# MCU_Power.net
KiCad netlist of a schematic drawn in Altium Designer
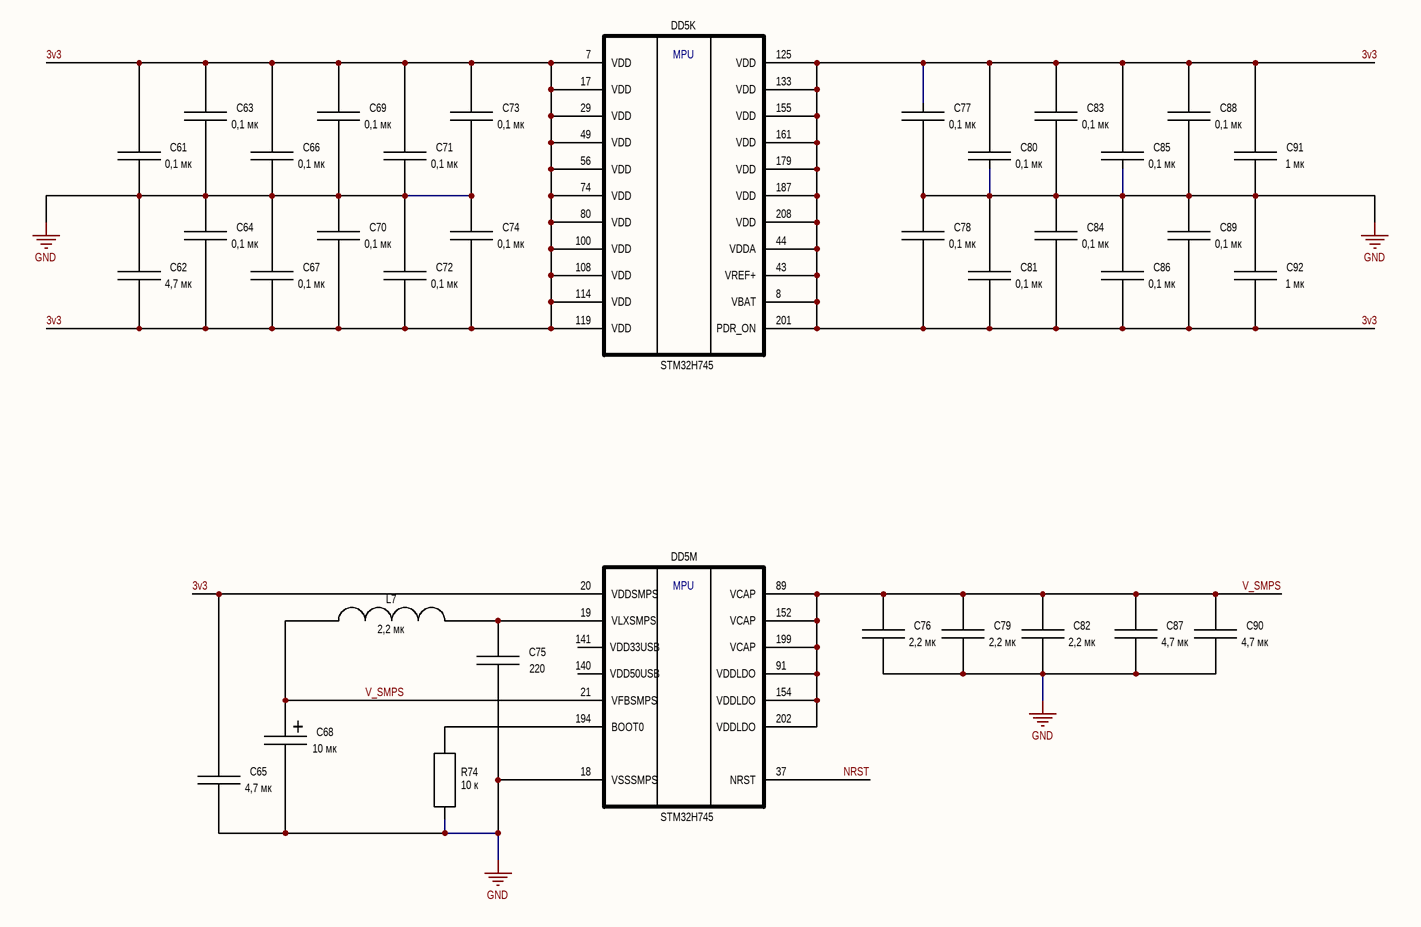
[diagram p0: MCU_Power.SchDoc]

(export (version "E")
  (design (tool "Eeschema 10.0.6"))
  (components
    (comp (ref "C61")
      (value "0,1 мк")
      (footprint "C0603")
      (fields
        (field (name "TOLERANCE") "±10%")
        (field (name "VOLTAGE") "50 В")
        (field (name "PARTNUMBER") "GRM188R71H104KA93D")
      )
      (libsource (lib "5ko") (part "C"))
    )
    (comp (ref "C62")
      (value "4,7 мк")
      (footprint "C0603")
      (fields
        (field (name "TOLERANCE") "±10%")
        (field (name "VOLTAGE") "16 В")
        (field (name "PARTNUMBER") "GRM188Z71C475KE21D")
      )
      (libsource (lib "5ko") (part "C"))
    )
    (comp (ref "C63")
      (value "0,1 мк")
      (footprint "C0603")
      (fields
        (field (name "TOLERANCE") "±10%")
        (field (name "VOLTAGE") "50 В")
        (field (name "PARTNUMBER") "GRM188R71H104KA93D")
      )
      (libsource (lib "5ko") (part "C"))
    )
    (comp (ref "C64")
      (value "0,1 мк")
      (footprint "C0603")
      (fields
        (field (name "TOLERANCE") "±10%")
        (field (name "VOLTAGE") "50 В")
        (field (name "PARTNUMBER") "GRM188R71H104KA93D")
      )
      (libsource (lib "5ko") (part "C"))
    )
    (comp (ref "C65")
      (value "4,7 мк")
      (footprint "C0603")
      (fields
        (field (name "TOLERANCE") "±10%")
        (field (name "VOLTAGE") "16 В")
        (field (name "PARTNUMBER") "GRM188Z71C475KE21D")
      )
      (libsource (lib "5ko") (part "C"))
    )
    (comp (ref "C66")
      (value "0,1 мк")
      (footprint "C0603")
      (fields
        (field (name "TOLERANCE") "±10%")
        (field (name "VOLTAGE") "50 В")
        (field (name "PARTNUMBER") "GRM188R71H104KA93D")
      )
      (libsource (lib "5ko") (part "C"))
    )
    (comp (ref "C67")
      (value "0,1 мк")
      (footprint "C0603")
      (fields
        (field (name "TOLERANCE") "±10%")
        (field (name "VOLTAGE") "50 В")
        (field (name "PARTNUMBER") "GRM188R71H104KA93D")
      )
      (libsource (lib "5ko") (part "C"))
    )
    (comp (ref "C68")
      (value "10 мк")
      (footprint "Case A")
      (fields
        (field (name "TOLERANCE") "±10%")
        (field (name "VOLTAGE") "16 V")
        (field (name "PARTNUMBER") "TAJA106K016RNJ")
      )
      (libsource (lib "5ko") (part "C_el"))
    )
    (comp (ref "C69")
      (value "0,1 мк")
      (footprint "C0603")
      (fields
        (field (name "TOLERANCE") "±10%")
        (field (name "VOLTAGE") "50 В")
        (field (name "PARTNUMBER") "GRM188R71H104KA93D")
      )
      (libsource (lib "5ko") (part "C"))
    )
    (comp (ref "C70")
      (value "0,1 мк")
      (footprint "C0603")
      (fields
        (field (name "TOLERANCE") "±10%")
        (field (name "VOLTAGE") "50 В")
        (field (name "PARTNUMBER") "GRM188R71H104KA93D")
      )
      (libsource (lib "5ko") (part "C"))
    )
    (comp (ref "C71")
      (value "0,1 мк")
      (footprint "C0603")
      (fields
        (field (name "TOLERANCE") "±10%")
        (field (name "VOLTAGE") "50 В")
        (field (name "PARTNUMBER") "GRM188R71H104KA93D")
      )
      (libsource (lib "5ko") (part "C"))
    )
    (comp (ref "C72")
      (value "0,1 мк")
      (footprint "C0603")
      (fields
        (field (name "TOLERANCE") "±10%")
        (field (name "VOLTAGE") "50 В")
        (field (name "PARTNUMBER") "GRM188R71H104KA93D")
      )
      (libsource (lib "5ko") (part "C"))
    )
    (comp (ref "C73")
      (value "0,1 мк")
      (footprint "C0603")
      (fields
        (field (name "TOLERANCE") "±10%")
        (field (name "VOLTAGE") "50 В")
        (field (name "PARTNUMBER") "GRM188R71H104KA93D")
      )
      (libsource (lib "5ko") (part "C"))
    )
    (comp (ref "C74")
      (value "0,1 мк")
      (footprint "C0603")
      (fields
        (field (name "TOLERANCE") "±10%")
        (field (name "VOLTAGE") "50 В")
        (field (name "PARTNUMBER") "GRM188R71H104KA93D")
      )
      (libsource (lib "5ko") (part "C"))
    )
    (comp (ref "C75")
      (value "220")
      (footprint "C0603")
      (fields
        (field (name "TOLERANCE") "±5%")
        (field (name "VOLTAGE") "100 В")
        (field (name "PARTNUMBER") "GCM1885C2A221JA16D")
      )
      (libsource (lib "5ko") (part "C"))
    )
    (comp (ref "C76")
      (value "2,2 мк")
      (footprint "C0603")
      (fields
        (field (name "TOLERANCE") "±10%")
        (field (name "VOLTAGE") "10 В")
        (field (name "PARTNUMBER") "GRM188R71A225KE15J")
      )
      (libsource (lib "5ko") (part "C"))
    )
    (comp (ref "C77")
      (value "0,1 мк")
      (footprint "C0603")
      (fields
        (field (name "TOLERANCE") "±10%")
        (field (name "VOLTAGE") "50 В")
        (field (name "PARTNUMBER") "GRM188R71H104KA93D")
      )
      (libsource (lib "5ko") (part "C"))
    )
    (comp (ref "C78")
      (value "0,1 мк")
      (footprint "C0603")
      (fields
        (field (name "TOLERANCE") "±10%")
        (field (name "VOLTAGE") "50 В")
        (field (name "PARTNUMBER") "GRM188R71H104KA93D")
      )
      (libsource (lib "5ko") (part "C"))
    )
    (comp (ref "C79")
      (value "2,2 мк")
      (footprint "C0603")
      (fields
        (field (name "TOLERANCE") "±10%")
        (field (name "VOLTAGE") "10 В")
        (field (name "PARTNUMBER") "GRM188R71A225KE15J")
      )
      (libsource (lib "5ko") (part "C"))
    )
    (comp (ref "C80")
      (value "0,1 мк")
      (footprint "C0603")
      (fields
        (field (name "TOLERANCE") "±10%")
        (field (name "VOLTAGE") "50 В")
        (field (name "PARTNUMBER") "GRM188R71H104KA93D")
      )
      (libsource (lib "5ko") (part "C"))
    )
    (comp (ref "C81")
      (value "0,1 мк")
      (footprint "C0603")
      (fields
        (field (name "TOLERANCE") "±10%")
        (field (name "VOLTAGE") "50 В")
        (field (name "PARTNUMBER") "GRM188R71H104KA93D")
      )
      (libsource (lib "5ko") (part "C"))
    )
    (comp (ref "C82")
      (value "2,2 мк")
      (footprint "C0603")
      (fields
        (field (name "TOLERANCE") "±10%")
        (field (name "VOLTAGE") "10 В")
        (field (name "PARTNUMBER") "GRM188R71A225KE15J")
      )
      (libsource (lib "5ko") (part "C"))
    )
    (comp (ref "C83")
      (value "0,1 мк")
      (footprint "C0603")
      (fields
        (field (name "TOLERANCE") "±10%")
        (field (name "VOLTAGE") "50 В")
        (field (name "PARTNUMBER") "GRM188R71H104KA93D")
      )
      (libsource (lib "5ko") (part "C"))
    )
    (comp (ref "C84")
      (value "0,1 мк")
      (footprint "C0603")
      (fields
        (field (name "TOLERANCE") "±10%")
        (field (name "VOLTAGE") "50 В")
        (field (name "PARTNUMBER") "GRM188R71H104KA93D")
      )
      (libsource (lib "5ko") (part "C"))
    )
    (comp (ref "C85")
      (value "0,1 мк")
      (footprint "C0603")
      (fields
        (field (name "TOLERANCE") "±10%")
        (field (name "VOLTAGE") "50 В")
        (field (name "PARTNUMBER") "GRM188R71H104KA93D")
      )
      (libsource (lib "5ko") (part "C"))
    )
    (comp (ref "C86")
      (value "0,1 мк")
      (footprint "C0603")
      (fields
        (field (name "TOLERANCE") "±10%")
        (field (name "VOLTAGE") "50 В")
        (field (name "PARTNUMBER") "GRM188R71H104KA93D")
      )
      (libsource (lib "5ko") (part "C"))
    )
    (comp (ref "C87")
      (value "4,7 мк")
      (footprint "C0603")
      (fields
        (field (name "TOLERANCE") "±10%")
        (field (name "VOLTAGE") "16 В")
        (field (name "PARTNUMBER") "GRM188Z71C475KE21D")
      )
      (libsource (lib "5ko") (part "C"))
    )
    (comp (ref "C88")
      (value "0,1 мк")
      (footprint "C0603")
      (fields
        (field (name "TOLERANCE") "±10%")
        (field (name "VOLTAGE") "50 В")
        (field (name "PARTNUMBER") "GRM188R71H104KA93D")
      )
      (libsource (lib "5ko") (part "C"))
    )
    (comp (ref "C89")
      (value "0,1 мк")
      (footprint "C0603")
      (fields
        (field (name "TOLERANCE") "±10%")
        (field (name "VOLTAGE") "50 В")
        (field (name "PARTNUMBER") "GRM188R71H104KA93D")
      )
      (libsource (lib "5ko") (part "C"))
    )
    (comp (ref "C90")
      (value "4,7 мк")
      (footprint "C0603")
      (fields
        (field (name "TOLERANCE") "±10%")
        (field (name "VOLTAGE") "16 В")
        (field (name "PARTNUMBER") "GRM188Z71C475KE21D")
      )
      (libsource (lib "5ko") (part "C"))
    )
    (comp (ref "C91")
      (value "1 мк")
      (footprint "C0603")
      (fields
        (field (name "TOLERANCE") "±10%")
        (field (name "VOLTAGE") "25 В")
        (field (name "PARTNUMBER") "GRM188R71E105KA12D")
      )
      (libsource (lib "5ko") (part "C"))
    )
    (comp (ref "C92")
      (value "1 мк")
      (footprint "C0603")
      (fields
        (field (name "TOLERANCE") "±10%")
        (field (name "VOLTAGE") "25 В")
        (field (name "PARTNUMBER") "GRM188R71E105KA12D")
      )
      (libsource (lib "5ko") (part "C"))
    )
    (comp (ref "DD5") (value "STM32H745") (footprint "LQFP208") (libsource (lib "5ko") (part "STM32H745")))
    (comp (ref "L7")
      (value "2,2 мк")
      (footprint "INDC_0603")
      (fields (field (name "PARTNUMBER") "MLZ1608A2R2WT000"))
      (libsource (lib "5ko") (part "L_1"))
    )
    (comp (ref "R74")
      (value "10 к")
      (footprint "R0603")
      (fields
        (field (name "TOLERANCE") "±5%")
        (field (name "POWER") "0.1 Вт")
        (field (name "PARTNUMBER") "RC0603JR-0710KL")
      )
      (libsource (lib "5ko") (part "R"))
    )
  )
  (nets
    (net (code "1") (name "/3v3") (class "Default")
      (node (ref "C61") (pin "1") (pinfunction "1_1") (pintype "passive"))
      (node (ref "C62") (pin "2") (pinfunction "2_2") (pintype "passive"))
      (node (ref "C63") (pin "1") (pinfunction "1_1") (pintype "passive"))
      (node (ref "C64") (pin "2") (pinfunction "2_2") (pintype "passive"))
      (node (ref "C65") (pin "1") (pinfunction "1_1") (pintype "passive"))
      (node (ref "C66") (pin "1") (pinfunction "1_1") (pintype "passive"))
      (node (ref "C67") (pin "2") (pinfunction "2_2") (pintype "passive"))
      (node (ref "C69") (pin "1") (pinfunction "1_1") (pintype "passive"))
      (node (ref "C70") (pin "2") (pinfunction "2_2") (pintype "passive"))
      (node (ref "C71") (pin "1") (pinfunction "1_1") (pintype "passive"))
      (node (ref "C72") (pin "2") (pinfunction "2_2") (pintype "passive"))
      (node (ref "C73") (pin "1") (pinfunction "1_1") (pintype "passive"))
      (node (ref "C74") (pin "2") (pinfunction "2_2") (pintype "passive"))
      (node (ref "C77") (pin "1") (pinfunction "1_1") (pintype "passive"))
      (node (ref "C78") (pin "2") (pinfunction "2_2") (pintype "passive"))
      (node (ref "C80") (pin "1") (pinfunction "1_1") (pintype "passive"))
      (node (ref "C81") (pin "2") (pinfunction "2_2") (pintype "passive"))
      (node (ref "C83") (pin "1") (pinfunction "1_1") (pintype "passive"))
      (node (ref "C84") (pin "2") (pinfunction "2_2") (pintype "passive"))
      (node (ref "C85") (pin "1") (pinfunction "1_1") (pintype "passive"))
      (node (ref "C86") (pin "2") (pinfunction "2_2") (pintype "passive"))
      (node (ref "C88") (pin "1") (pinfunction "1_1") (pintype "passive"))
      (node (ref "C89") (pin "2") (pinfunction "2_2") (pintype "passive"))
      (node (ref "C91") (pin "1") (pinfunction "1_1") (pintype "passive"))
      (node (ref "C92") (pin "2") (pinfunction "2_2") (pintype "passive"))
      (node (ref "DD5") (pin "100") (pinfunction "VDD_100") (pintype "passive"))
      (node (ref "DD5") (pin "108") (pinfunction "VDD_108") (pintype "passive"))
      (node (ref "DD5") (pin "114") (pinfunction "VDD_114") (pintype "passive"))
      (node (ref "DD5") (pin "119") (pinfunction "VDD_119") (pintype "passive"))
      (node (ref "DD5") (pin "125") (pinfunction "VDD_125") (pintype "passive"))
      (node (ref "DD5") (pin "133") (pinfunction "VDD_133") (pintype "passive"))
      (node (ref "DD5") (pin "155") (pinfunction "VDD_155") (pintype "passive"))
      (node (ref "DD5") (pin "161") (pinfunction "VDD_161") (pintype "passive"))
      (node (ref "DD5") (pin "17") (pinfunction "VDD_17") (pintype "passive"))
      (node (ref "DD5") (pin "179") (pinfunction "VDD_179") (pintype "passive"))
      (node (ref "DD5") (pin "187") (pinfunction "VDD_187") (pintype "passive"))
      (node (ref "DD5") (pin "20") (pinfunction "VDDSMPS_20") (pintype "passive"))
      (node (ref "DD5") (pin "201") (pinfunction "PDR_ON_201") (pintype "passive"))
      (node (ref "DD5") (pin "208") (pinfunction "VDD_208") (pintype "passive"))
      (node (ref "DD5") (pin "29") (pinfunction "VDD_29") (pintype "passive"))
      (node (ref "DD5") (pin "43") (pinfunction "VREF+_43") (pintype "passive"))
      (node (ref "DD5") (pin "44") (pinfunction "VDDA_44") (pintype "passive"))
      (node (ref "DD5") (pin "49") (pinfunction "VDD_49") (pintype "passive"))
      (node (ref "DD5") (pin "56") (pinfunction "VDD_56") (pintype "passive"))
      (node (ref "DD5") (pin "7") (pinfunction "VDD_7") (pintype "passive"))
      (node (ref "DD5") (pin "74") (pinfunction "VDD_74") (pintype "passive"))
      (node (ref "DD5") (pin "8") (pinfunction "VBAT_8") (pintype "passive"))
      (node (ref "DD5") (pin "80") (pinfunction "VDD_80") (pintype "passive"))
    )
    (net (code "2") (name "/NRST") (class "Default")
      (node (ref "DD5") (pin "37") (pinfunction "NRST_37") (pintype "passive"))
    )
    (net (code "3") (name "/V_SMPS") (class "Default")
      (node (ref "C68") (pin "1") (pinfunction "1_1") (pintype "passive"))
      (node (ref "C76") (pin "1") (pinfunction "1_1") (pintype "passive"))
      (node (ref "C79") (pin "1") (pinfunction "1_1") (pintype "passive"))
      (node (ref "C82") (pin "1") (pinfunction "1_1") (pintype "passive"))
      (node (ref "C87") (pin "1") (pinfunction "1_1") (pintype "passive"))
      (node (ref "C90") (pin "1") (pinfunction "1_1") (pintype "passive"))
      (node (ref "DD5") (pin "152") (pinfunction "VCAP_152") (pintype "passive"))
      (node (ref "DD5") (pin "154") (pinfunction "VDDLDO_154") (pintype "passive"))
      (node (ref "DD5") (pin "199") (pinfunction "VCAP_199") (pintype "passive"))
      (node (ref "DD5") (pin "202") (pinfunction "VDDLDO_202") (pintype "passive"))
      (node (ref "DD5") (pin "21") (pinfunction "VFBSMPS_21") (pintype "passive"))
      (node (ref "DD5") (pin "89") (pinfunction "VCAP_89") (pintype "passive"))
      (node (ref "DD5") (pin "91") (pinfunction "VDDLDO_91") (pintype "passive"))
      (node (ref "L7") (pin "2") (pinfunction "2_2") (pintype "passive"))
    )
    (net (code "4") (name "GND") (class "Default")
      (node (ref "C61") (pin "2") (pinfunction "2_2") (pintype "passive"))
      (node (ref "C62") (pin "1") (pinfunction "1_1") (pintype "passive"))
      (node (ref "C63") (pin "2") (pinfunction "2_2") (pintype "passive"))
      (node (ref "C64") (pin "1") (pinfunction "1_1") (pintype "passive"))
      (node (ref "C65") (pin "2") (pinfunction "2_2") (pintype "passive"))
      (node (ref "C66") (pin "2") (pinfunction "2_2") (pintype "passive"))
      (node (ref "C67") (pin "1") (pinfunction "1_1") (pintype "passive"))
      (node (ref "C68") (pin "2") (pinfunction "2_2") (pintype "passive"))
      (node (ref "C69") (pin "2") (pinfunction "2_2") (pintype "passive"))
      (node (ref "C70") (pin "1") (pinfunction "1_1") (pintype "passive"))
      (node (ref "C71") (pin "2") (pinfunction "2_2") (pintype "passive"))
      (node (ref "C72") (pin "1") (pinfunction "1_1") (pintype "passive"))
      (node (ref "C73") (pin "2") (pinfunction "2_2") (pintype "passive"))
      (node (ref "C74") (pin "1") (pinfunction "1_1") (pintype "passive"))
      (node (ref "C75") (pin "2") (pinfunction "2_2") (pintype "passive"))
      (node (ref "C76") (pin "2") (pinfunction "2_2") (pintype "passive"))
      (node (ref "C77") (pin "2") (pinfunction "2_2") (pintype "passive"))
      (node (ref "C78") (pin "1") (pinfunction "1_1") (pintype "passive"))
      (node (ref "C79") (pin "2") (pinfunction "2_2") (pintype "passive"))
      (node (ref "C80") (pin "2") (pinfunction "2_2") (pintype "passive"))
      (node (ref "C81") (pin "1") (pinfunction "1_1") (pintype "passive"))
      (node (ref "C82") (pin "2") (pinfunction "2_2") (pintype "passive"))
      (node (ref "C83") (pin "2") (pinfunction "2_2") (pintype "passive"))
      (node (ref "C84") (pin "1") (pinfunction "1_1") (pintype "passive"))
      (node (ref "C85") (pin "2") (pinfunction "2_2") (pintype "passive"))
      (node (ref "C86") (pin "1") (pinfunction "1_1") (pintype "passive"))
      (node (ref "C87") (pin "2") (pinfunction "2_2") (pintype "passive"))
      (node (ref "C88") (pin "2") (pinfunction "2_2") (pintype "passive"))
      (node (ref "C89") (pin "1") (pinfunction "1_1") (pintype "passive"))
      (node (ref "C90") (pin "2") (pinfunction "2_2") (pintype "passive"))
      (node (ref "C91") (pin "2") (pinfunction "2_2") (pintype "passive"))
      (node (ref "C92") (pin "1") (pinfunction "1_1") (pintype "passive"))
      (node (ref "DD5") (pin "18") (pinfunction "VSSSMPS_18") (pintype "passive"))
      (node (ref "R74") (pin "1") (pinfunction "1_1") (pintype "passive"))
    )
    (net (code "5") (name "Net-(DD5M-BOOT0)") (class "Default")
      (node (ref "DD5") (pin "194") (pinfunction "BOOT0_194") (pintype "passive"))
      (node (ref "R74") (pin "2") (pinfunction "2_2") (pintype "passive"))
    )
    (net (code "6") (name "Net-(DD5M-VLXSMPS)") (class "Default")
      (node (ref "C75") (pin "1") (pinfunction "1_1") (pintype "passive"))
      (node (ref "DD5") (pin "19") (pinfunction "VLXSMPS_19") (pintype "passive"))
      (node (ref "L7") (pin "1") (pinfunction "1_1") (pintype "passive"))
    )
    (net (code "7") (name "unconnected-(DD5M-VDD33USB-Pad141)") (class "Default")
      (node (ref "DD5") (pin "141") (pinfunction "VDD33USB_141") (pintype "passive"))
    )
    (net (code "8") (name "unconnected-(DD5M-VDD50USB-Pad140)") (class "Default")
      (node (ref "DD5") (pin "140") (pinfunction "VDD50USB_140") (pintype "passive"))
    )
  )
)
